# Module_blk.net
KiCad netlist of a schematic drawn in Altium Designer
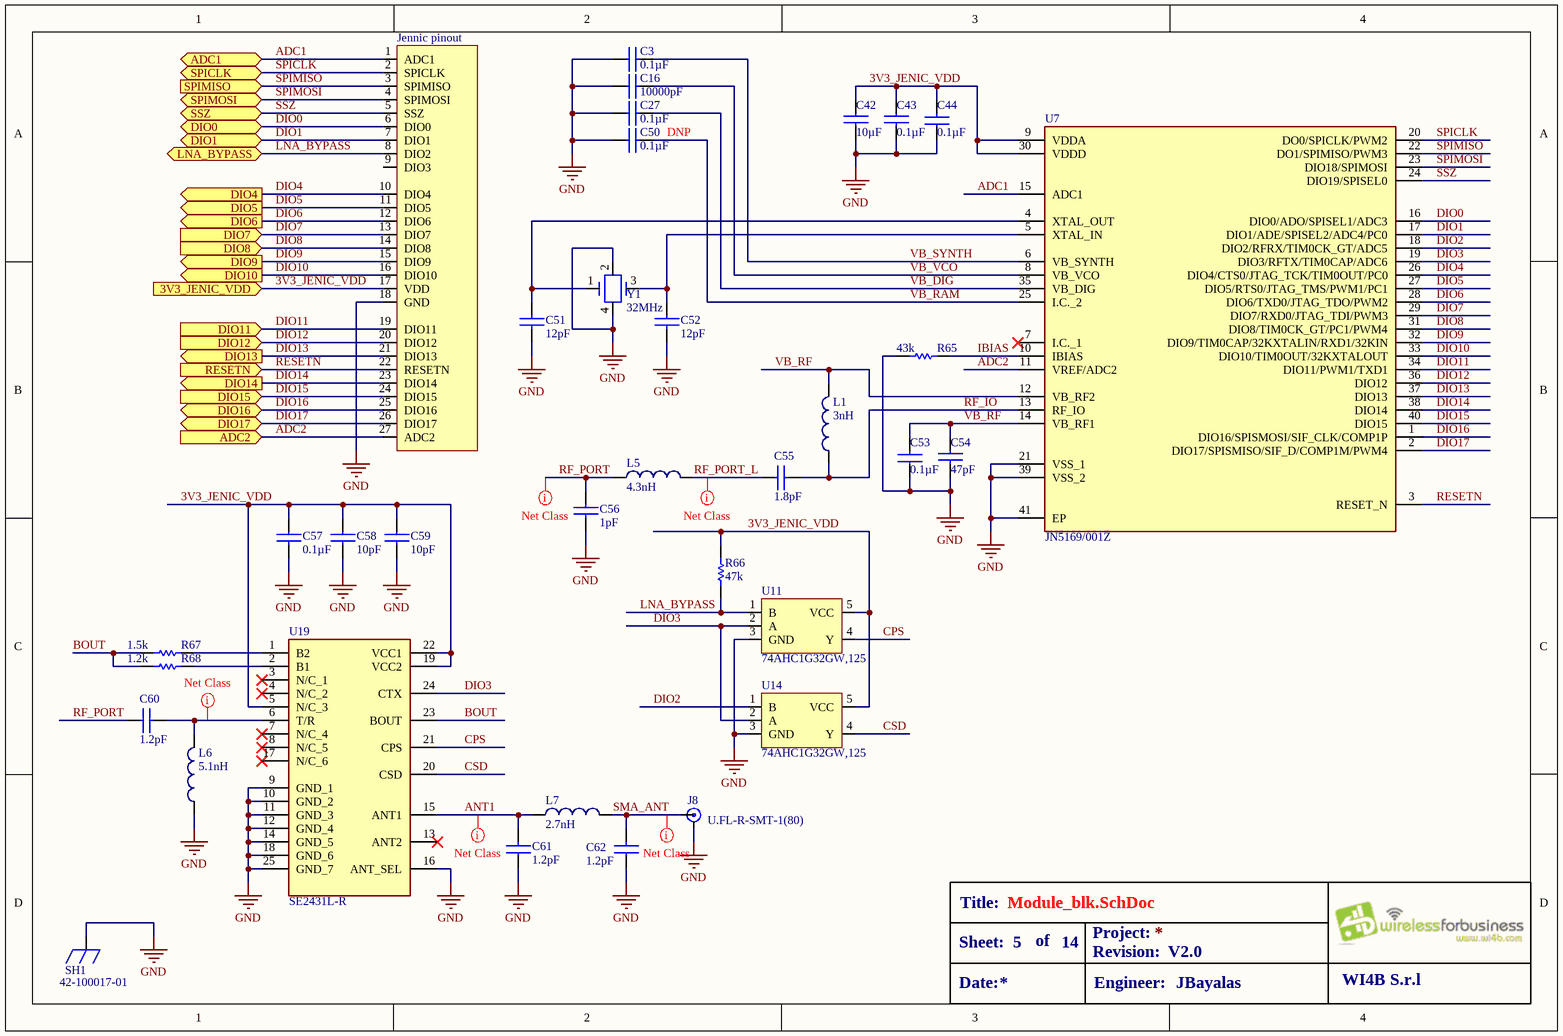
[diagram p0: Module_blk.SchDoc]

(export (version "E")
  (design (tool "Eeschema 10.0.6"))
  (components
    (comp (ref "C3")
      (value "0.1µF")
      (footprint "C0402")
      (description "CAP CER 0.1UF 50V X7R 0402")
      (fields (field (name "MPN") "GRM155R71H104ME14D"))
      (libsource (lib "Capacitor") (part "GRM155R71H104ME14D"))
    )
    (comp (ref "C16")
      (value "10000pF")
      (footprint "C0402")
      (description "CAP CER 10000PF 25V X7R 0402")
      (fields (field (name "MPN") "GRM155R71E103KA01D"))
      (libsource (lib "Capacitor") (part "GRM155R71E103KA01D"))
    )
    (comp (ref "C27")
      (value "0.1µF")
      (footprint "C0402")
      (description "CAP CER 0.1UF 50V X7R 0402")
      (fields (field (name "MPN") "GRM155R71H104ME14D"))
      (libsource (lib "Capacitor") (part "GRM155R71H104ME14D"))
    )
    (comp (ref "C42")
      (value "10µF")
      (footprint "CAPC2012X135N")
      (description "CAP CER 10UF 10V X5R 0805")
      (fields (field (name "MPN") "GRT21BR61A106KE01L"))
      (libsource (lib "Capacitor") (part "GRT21BR61A106KE01L"))
    )
    (comp (ref "C43")
      (value "0.1µF")
      (footprint "C0402")
      (description "CAP CER 0.1UF 50V X7R 0402")
      (fields (field (name "MPN") "GRM155R71H104ME14D"))
      (libsource (lib "Capacitor") (part "GRM155R71H104ME14D"))
    )
    (comp (ref "C44")
      (value "0.1µF")
      (footprint "C0402")
      (description "CAP CER 0.1UF 50V X7R 0402")
      (fields (field (name "MPN") "GRM155R71H104ME14D"))
      (libsource (lib "Capacitor") (part "GRM155R71H104ME14D"))
    )
    (comp (ref "C50")
      (value "0.1µF")
      (footprint "C0402")
      (description "CAP CER 0.1UF 50V X7R 0402")
      (fields (field (name "MPN") "GRM155R71H104ME14D") (field (name "LOAD") "DNP"))
      (libsource (lib "Capacitor") (part "GRM155R71H104ME14D"))
    )
    (comp (ref "C51")
      (value "12pF")
      (footprint "CAPC1005X55N")
      (description "CAP CER 12PF 50V C0G/NP0 0402")
      (fields (field (name "MPN") "GRM1555C1H120JA01D"))
      (libsource (lib "Capacitor") (part "GRM1555C1H120JA01D"))
    )
    (comp (ref "C52")
      (value "12pF")
      (footprint "CAPC1005X55N")
      (description "CAP CER 12PF 50V C0G/NP0 0402")
      (fields (field (name "MPN") "GRM1555C1H120JA01D"))
      (libsource (lib "Capacitor") (part "GRM1555C1H120JA01D"))
    )
    (comp (ref "C53")
      (value "0.1µF")
      (footprint "C0402")
      (description "CAP CER 0.1UF 50V X7R 0402")
      (fields (field (name "MPN") "GRM155R71H104ME14D"))
      (libsource (lib "Capacitor") (part "GRM155R71H104ME14D"))
    )
    (comp (ref "C54")
      (value "47pF")
      (footprint "CAPC1005X55N")
      (description "CAP CER 47PF 50V C0G/NP0 0402")
      (fields (field (name "MPN") "GRM1555C1H470JA01D"))
      (libsource (lib "Capacitor") (part "GRM1555C1H470JA01D"))
    )
    (comp (ref "C55")
      (value "1.8pF")
      (footprint "CAPC1005X55N")
      (description "CAP CER 1.8PF 50V C0G/NP0 0402")
      (fields (field (name "MPN") "GRM1555C1H1R8CA01D"))
      (libsource (lib "Capacitor") (part "GRM1555C1H1R8CA01D"))
    )
    (comp (ref "C56")
      (value "1pF")
      (footprint "CAPC1005X55N")
      (description "CAP CER 1PF 50V C0G/NP0 0402")
      (fields (field (name "MPN") "GRM1555C1H1R0CA01D"))
      (libsource (lib "Capacitor") (part "GRM1555C1H1R0CA01D"))
    )
    (comp (ref "C57")
      (value "0.1µF")
      (footprint "C0402")
      (description "CAP CER 0.1UF 50V X7R 0402")
      (fields (field (name "MPN") "GRM155R71H104ME14D"))
      (libsource (lib "Capacitor") (part "GRM155R71H104ME14D"))
    )
    (comp (ref "C58")
      (value "10pF")
      (footprint "C0402")
      (description "CAP CER 10PF 50V 5% NP0 0402")
      (fields (field (name "MPN") "GRM1555C1H100JA01D"))
      (libsource (lib "Capacitor") (part "GRM1555C1H100JA01D"))
    )
    (comp (ref "C59")
      (value "10pF")
      (footprint "C0402")
      (description "CAP CER 10PF 50V 5% NP0 0402")
      (fields (field (name "MPN") "GRM1555C1H100JA01D"))
      (libsource (lib "Capacitor") (part "GRM1555C1H100JA01D"))
    )
    (comp (ref "C60")
      (value "1.2pF")
      (footprint "CAPC1005X55N")
      (description "CAP CER 1.2PF 50V C0G/NP0 0402")
      (fields (field (name "MPN") "GRM1555C1H1R2CA01D"))
      (libsource (lib "Capacitor") (part "GRM1555C1H1R2CA01D"))
    )
    (comp (ref "C61")
      (value "1.2pF")
      (footprint "CAPC1005X55N")
      (description "CAP CER 1.2PF 50V C0G/NP0 0402")
      (fields (field (name "MPN") "GRM1555C1H1R2CA01D"))
      (libsource (lib "Capacitor") (part "GRM1555C1H1R2CA01D"))
    )
    (comp (ref "C62")
      (value "1.2pF")
      (footprint "CAPC1005X55N")
      (description "CAP CER 1.2PF 50V C0G/NP0 0402")
      (fields (field (name "MPN") "GRM1555C1H1R2CA01D"))
      (libsource (lib "Capacitor") (part "GRM1555C1H1R2CA01D"))
    )
    (comp (ref "J8")
      (value "U.FL-R-SMT-1(80)")
      (footprint "HIROSE_U.FL-R-SMT")
      (description "RF Connectors / Coaxial Connectors SMT MALE RECEPT AU")
      (libsource (lib "Connector") (part "U.FL-R-SMT-1(80)"))
    )
    (comp (ref "Jennic pinout")
      (value "Jennic pinout")
      (footprint "JN516X PINOUT")
      (fields (field (name "MPN") "Jennic Pinout"))
      (libsource (lib "Miscellaneous") (part "Jennic pinout"))
    )
    (comp (ref "L1")
      (value "3nH")
      (footprint "INDC1005X45N")
      (description "FIXED IND 3NH 190MA 400 MOHM SMD")
      (fields (field (name "MPN") "LQP15MN3N0B02D"))
      (libsource (lib "Inductor") (part "LQP15MN3N0B02D"))
    )
    (comp (ref "L5")
      (value "4.3nH")
      (footprint "INDC1005X45N")
      (description "FIXED IND 4.3NH 160MA 600 MOHM")
      (fields (field (name "MPN") "LQP15MN4N3B02D"))
      (libsource (lib "Inductor") (part "LQP15MN4N3B02D"))
    )
    (comp (ref "L6")
      (value "5.1nH")
      (footprint "INDC1005X45N")
      (description "Inductor RF Chip ThFIXED IND 5.1NH 140MA 700 MOHM")
      (fields (field (name "MPN") "LQP15MN5N1B02D"))
      (libsource (lib "Inductor") (part "LQP15MN5N1B02D"))
    )
    (comp (ref "L7")
      (value "2.7nH")
      (footprint "INDC1005X45N")
      (description "FIXED IND 2.7NH 220MA 300 MOHM")
      (fields (field (name "MPN") "LQP15MN2N7B02D"))
      (libsource (lib "Inductor") (part "LQP15MN2N7B02D"))
    )
    (comp (ref "R65")
      (value "43k")
      (footprint "RESC1005X40N")
      (description "RES SMD 43K OHM 1% 1/16W 0402")
      (fields (field (name "MPN") "RC0402FR-0743KL"))
      (libsource (lib "Res") (part "RC0402FR-0743KL"))
    )
    (comp (ref "R66")
      (value "47k")
      (footprint "R0402")
      (description "RES SMD 47K OHM 1% 1/16W 0402")
      (fields (field (name "MPN") "RC0402FR-0747KL"))
      (libsource (lib "Res") (part "RC0402FR-0747KL"))
    )
    (comp (ref "R67")
      (value "1.5k")
      (footprint "RESC1005X40N")
      (description "RES SMD 1.5K OHM 1% 1/16W 0402")
      (fields (field (name "MPN") "RC0402FR-071K5L"))
      (libsource (lib "Res") (part "RC0402FR-071K5L"))
    )
    (comp (ref "R68")
      (value "1.2k")
      (footprint "RESC1005X40N")
      (description "RES SMD 1.2K OHM 1% 1/16W 0402")
      (fields (field (name "MPN") "RC0402FR-071K2L"))
      (libsource (lib "Res") (part "RC0402FR-071K2L"))
    )
    (comp (ref "SH1")
      (value "42-100017-01")
      (footprint "42-100017-01(Shield)")
      (description "Shield")
      (libsource (lib "Miscellaneous") (part "42-100017-01"))
    )
    (comp (ref "U7")
      (value "JN5169/001Z")
      (footprint "QFN50P600X600X100-41N")
      (description "IC RF TXRX+MCU 802.15.4 40-VFQFN")
      (libsource (lib "IC") (part "JN5169/001Z"))
    )
    (comp (ref "U11")
      (value "74AHC1G32GW,125")
      (footprint "SOT65P210X110-5N")
      (description "IC GATE OR 1CH 2-INP 5TSSOP")
      (libsource (lib "IC") (part "74AHC1G32GW,125"))
    )
    (comp (ref "U14")
      (value "74AHC1G32GW,125")
      (footprint "SOT65P210X110-5N")
      (description "IC GATE OR 1CH 2-INP 5TSSOP")
      (libsource (lib "IC") (part "74AHC1G32GW,125"))
    )
    (comp (ref "U19")
      (value "SE2431L-R")
      (footprint "QFN40P300X400X90-25N-D")
      (description "IC RF FRONT END MOD 2.4GHZ 24QFN")
      (libsource (lib "IC") (part "SE2431L-R"))
    )
    (comp (ref "Y1")
      (value "32MHz")
      (footprint "OSCCC320X250X80L75X100N")
      (description "CRYSTAL 32.0000MHZ 9PF SMD")
      (fields (field (name "MPN") "ABM8-32.000MHZ-9-D1G-T"))
      (libsource (lib "Crystal") (part "ABM8-32.000MHZ-9-D1G-T"))
    )
  )
  (nets
    (net (code "1") (name "/3V3_JENIC_VDD") (class "Default")
      (node (ref "C42") (pin "1") (pinfunction "1_1") (pintype "passive"))
      (node (ref "C43") (pin "1") (pinfunction "1_1") (pintype "passive"))
      (node (ref "C44") (pin "2") (pinfunction "2_2") (pintype "passive"))
      (node (ref "C57") (pin "1") (pinfunction "1_1") (pintype "passive"))
      (node (ref "C58") (pin "1") (pinfunction "1_1") (pintype "passive"))
      (node (ref "C59") (pin "1") (pinfunction "1_1") (pintype "passive"))
      (node (ref "Jennic pinout") (pin "17") (pinfunction "VDD_17") (pintype "passive"))
      (node (ref "R66") (pin "2") (pinfunction "2_2") (pintype "passive"))
      (node (ref "U11") (pin "5") (pinfunction "VCC_5") (pintype "passive"))
      (node (ref "U14") (pin "5") (pinfunction "VCC_5") (pintype "passive"))
      (node (ref "U19") (pin "19") (pinfunction "VCC2_19") (pintype "passive"))
      (node (ref "U19") (pin "22") (pinfunction "VCC1_22") (pintype "passive"))
      (node (ref "U19") (pin "5") (pinfunction "N/C_3_5") (pintype "passive"))
      (node (ref "U7") (pin "30") (pinfunction "VDDD_30") (pintype "passive"))
      (node (ref "U7") (pin "9") (pinfunction "VDDA_9") (pintype "passive"))
    )
    (net (code "2") (name "/ADC1") (class "Default")
      (node (ref "Jennic pinout") (pin "1") (pinfunction "ADC1_1") (pintype "passive"))
      (node (ref "U7") (pin "15") (pinfunction "ADC1_15") (pintype "passive"))
    )
    (net (code "3") (name "/ADC2") (class "Default")
      (node (ref "Jennic pinout") (pin "27") (pinfunction "ADC2_27") (pintype "passive"))
      (node (ref "U7") (pin "11") (pinfunction "VREF/ADC2_11") (pintype "passive"))
    )
    (net (code "4") (name "/ANT1") (class "Default")
      (node (ref "C61") (pin "2") (pinfunction "2_2") (pintype "passive"))
      (node (ref "L7") (pin "2") (pinfunction "2_2") (pintype "passive"))
      (node (ref "U19") (pin "15") (pinfunction "ANT1_15") (pintype "passive"))
    )
    (net (code "5") (name "/BOUT") (class "Default")
      (node (ref "R67") (pin "1") (pinfunction "1_1") (pintype "passive"))
      (node (ref "R68") (pin "1") (pinfunction "1_1") (pintype "passive"))
      (node (ref "U19") (pin "23") (pinfunction "BOUT_23") (pintype "passive"))
    )
    (net (code "6") (name "/CPS") (class "Default")
      (node (ref "U11") (pin "4") (pinfunction "Y_4") (pintype "passive"))
      (node (ref "U19") (pin "21") (pinfunction "CPS_21") (pintype "passive"))
    )
    (net (code "7") (name "/CSD") (class "Default")
      (node (ref "U14") (pin "4") (pinfunction "Y_4") (pintype "passive"))
      (node (ref "U19") (pin "20") (pinfunction "CSD_20") (pintype "passive"))
    )
    (net (code "8") (name "/DIO0") (class "Default")
      (node (ref "Jennic pinout") (pin "6") (pinfunction "DIO0_6") (pintype "passive"))
      (node (ref "U7") (pin "16") (pinfunction "DIO0/ADO/SPISEL1/ADC3_16") (pintype "passive"))
    )
    (net (code "9") (name "/DIO1") (class "Default")
      (node (ref "Jennic pinout") (pin "7") (pinfunction "DIO1_7") (pintype "passive"))
      (node (ref "U7") (pin "17") (pinfunction "DIO1/ADE/SPISEL2/ADC4/PC0_17") (pintype "passive"))
    )
    (net (code "10") (name "/DIO2") (class "Default")
      (node (ref "U14") (pin "1") (pinfunction "B_1") (pintype "passive"))
      (node (ref "U7") (pin "18") (pinfunction "DIO2/RFRX/TIM0CK_GT/ADC5_18") (pintype "passive"))
    )
    (net (code "11") (name "/DIO3") (class "Default")
      (node (ref "U11") (pin "2") (pinfunction "A_2") (pintype "passive"))
      (node (ref "U14") (pin "2") (pinfunction "A_2") (pintype "passive"))
      (node (ref "U19") (pin "24") (pinfunction "CTX_24") (pintype "passive"))
      (node (ref "U7") (pin "19") (pinfunction "DIO3/RFTX/TIM0CAP/ADC6_19") (pintype "passive"))
    )
    (net (code "12") (name "/DIO4") (class "Default")
      (node (ref "Jennic pinout") (pin "10") (pinfunction "DIO4_10") (pintype "passive"))
      (node (ref "U7") (pin "26") (pinfunction "DIO4/CTS0/JTAG_TCK/TIM0OUT/PC0_26") (pintype "passive"))
    )
    (net (code "13") (name "/DIO5") (class "Default")
      (node (ref "Jennic pinout") (pin "11") (pinfunction "DIO5_11") (pintype "passive"))
      (node (ref "U7") (pin "27") (pinfunction "DIO5/RTS0/JTAG_TMS/PWM1/PC1_27") (pintype "passive"))
    )
    (net (code "14") (name "/DIO6") (class "Default")
      (node (ref "Jennic pinout") (pin "12") (pinfunction "DIO6_12") (pintype "passive"))
      (node (ref "U7") (pin "28") (pinfunction "DIO6/TXD0/JTAG_TDO/PWM2_28") (pintype "passive"))
    )
    (net (code "15") (name "/DIO7") (class "Default")
      (node (ref "Jennic pinout") (pin "13") (pinfunction "DIO7_13") (pintype "passive"))
      (node (ref "U7") (pin "29") (pinfunction "DIO7/RXD0/JTAG_TDI/PWM3_29") (pintype "passive"))
    )
    (net (code "16") (name "/DIO8") (class "Default")
      (node (ref "Jennic pinout") (pin "14") (pinfunction "DIO8_14") (pintype "passive"))
      (node (ref "U7") (pin "31") (pinfunction "DIO8/TIM0CK_GT/PC1/PWM4_31") (pintype "passive"))
    )
    (net (code "17") (name "/DIO9") (class "Default")
      (node (ref "Jennic pinout") (pin "15") (pinfunction "DIO9_15") (pintype "passive"))
      (node (ref "U7") (pin "32") (pinfunction "DIO9/TIM0CAP/32KXTALIN/RXD1/32KIN_32") (pintype "passive"))
    )
    (net (code "18") (name "/DIO10") (class "Default")
      (node (ref "Jennic pinout") (pin "16") (pinfunction "DIO10_16") (pintype "passive"))
      (node (ref "U7") (pin "33") (pinfunction "DIO10/TIM0OUT/32KXTALOUT_33") (pintype "passive"))
    )
    (net (code "19") (name "/DIO11") (class "Default")
      (node (ref "Jennic pinout") (pin "19") (pinfunction "DIO11_19") (pintype "passive"))
      (node (ref "U7") (pin "34") (pinfunction "DIO11/PWM1/TXD1_34") (pintype "passive"))
    )
    (net (code "20") (name "/DIO12") (class "Default")
      (node (ref "Jennic pinout") (pin "20") (pinfunction "DIO12_20") (pintype "passive"))
      (node (ref "U7") (pin "36") (pinfunction "DIO12_36") (pintype "passive"))
    )
    (net (code "21") (name "/DIO13") (class "Default")
      (node (ref "Jennic pinout") (pin "21") (pinfunction "DIO13_21") (pintype "passive"))
      (node (ref "U7") (pin "37") (pinfunction "DIO13_37") (pintype "passive"))
    )
    (net (code "22") (name "/DIO14") (class "Default")
      (node (ref "Jennic pinout") (pin "23") (pinfunction "DIO14_23") (pintype "passive"))
      (node (ref "U7") (pin "38") (pinfunction "DIO14_38") (pintype "passive"))
    )
    (net (code "23") (name "/DIO15") (class "Default")
      (node (ref "Jennic pinout") (pin "24") (pinfunction "DIO15_24") (pintype "passive"))
      (node (ref "U7") (pin "40") (pinfunction "DIO15_40") (pintype "passive"))
    )
    (net (code "24") (name "/DIO16") (class "Default")
      (node (ref "Jennic pinout") (pin "25") (pinfunction "DIO16_25") (pintype "passive"))
      (node (ref "U7") (pin "1") (pinfunction "DIO16/SPISMOSI/SIF_CLK/COMP1P_1") (pintype "passive"))
    )
    (net (code "25") (name "/DIO17") (class "Default")
      (node (ref "Jennic pinout") (pin "26") (pinfunction "DIO17_26") (pintype "passive"))
      (node (ref "U7") (pin "2") (pinfunction "DIO17/SPISMISO/SIF_D/COMP1M/PWM4_2") (pintype "passive"))
    )
    (net (code "26") (name "/IBIAS") (class "Default")
      (node (ref "R65") (pin "2") (pinfunction "2_2") (pintype "passive"))
      (node (ref "U7") (pin "10") (pinfunction "IBIAS_10") (pintype "passive"))
    )
    (net (code "27") (name "/LNA_BYPASS") (class "Default")
      (node (ref "Jennic pinout") (pin "8") (pinfunction "DIO2_8") (pintype "passive"))
      (node (ref "R66") (pin "1") (pinfunction "1_1") (pintype "passive"))
      (node (ref "U11") (pin "1") (pinfunction "B_1") (pintype "passive"))
    )
    (net (code "28") (name "/RESETN") (class "Default")
      (node (ref "Jennic pinout") (pin "22") (pinfunction "RESETN_22") (pintype "passive"))
      (node (ref "U7") (pin "3") (pinfunction "RESET_N_3") (pintype "passive"))
    )
    (net (code "29") (name "/RF_IO") (class "Default")
      (node (ref "C55") (pin "2") (pinfunction "2_2") (pintype "passive"))
      (node (ref "L1") (pin "2") (pinfunction "2_2") (pintype "passive"))
      (node (ref "U7") (pin "13") (pinfunction "RF_IO_13") (pintype "passive"))
    )
    (net (code "30") (name "/RF_PORT") (class "Default")
      (node (ref "C56") (pin "1") (pinfunction "1_1") (pintype "passive"))
      (node (ref "C60") (pin "1") (pinfunction "1_1") (pintype "passive"))
      (node (ref "L5") (pin "2") (pinfunction "2_2") (pintype "passive"))
    )
    (net (code "31") (name "/RF_PORT_L") (class "Default")
      (node (ref "C55") (pin "1") (pinfunction "1_1") (pintype "passive"))
      (node (ref "L5") (pin "1") (pinfunction "1_1") (pintype "passive"))
    )
    (net (code "32") (name "/SMA_ANT") (class "Default")
      (node (ref "C62") (pin "2") (pinfunction "2_2") (pintype "passive"))
      (node (ref "J8") (pin "1") (pinfunction "SIGNAL_1") (pintype "passive"))
      (node (ref "L7") (pin "1") (pinfunction "1_1") (pintype "passive"))
    )
    (net (code "33") (name "/SPICLK") (class "Default")
      (node (ref "Jennic pinout") (pin "2") (pinfunction "SPICLK_2") (pintype "passive"))
      (node (ref "U7") (pin "20") (pinfunction "DO0/SPICLK/PWM2_20") (pintype "passive"))
    )
    (net (code "34") (name "/SPIMISO") (class "Default")
      (node (ref "Jennic pinout") (pin "3") (pinfunction "SPIMISO_3") (pintype "passive"))
      (node (ref "U7") (pin "22") (pinfunction "DO1/SPIMISO/PWM3_22") (pintype "passive"))
    )
    (net (code "35") (name "/SPIMOSI") (class "Default")
      (node (ref "Jennic pinout") (pin "4") (pinfunction "SPIMOSI_4") (pintype "passive"))
      (node (ref "U7") (pin "23") (pinfunction "DIO18/SPIMOSI_23") (pintype "passive"))
    )
    (net (code "36") (name "/SSZ") (class "Default")
      (node (ref "Jennic pinout") (pin "5") (pinfunction "SSZ_5") (pintype "passive"))
      (node (ref "U7") (pin "24") (pinfunction "DIO19/SPISEL0_24") (pintype "passive"))
    )
    (net (code "37") (name "/VB_DIG") (class "Default")
      (node (ref "C27") (pin "2") (pinfunction "2_2") (pintype "passive"))
      (node (ref "U7") (pin "35") (pinfunction "VB_DIG_35") (pintype "passive"))
    )
    (net (code "38") (name "/VB_RAM") (class "Default")
      (node (ref "C50") (pin "2") (pinfunction "2_2") (pintype "passive"))
      (node (ref "U7") (pin "25") (pinfunction "I.C._2_25") (pintype "passive"))
    )
    (net (code "39") (name "/VB_RF") (class "Default")
      (node (ref "C53") (pin "2") (pinfunction "2_2") (pintype "passive"))
      (node (ref "C54") (pin "1") (pinfunction "1_1") (pintype "passive"))
      (node (ref "L1") (pin "1") (pinfunction "1_1") (pintype "passive"))
      (node (ref "U7") (pin "12") (pinfunction "VB_RF2_12") (pintype "passive"))
      (node (ref "U7") (pin "14") (pinfunction "VB_RF1_14") (pintype "passive"))
    )
    (net (code "40") (name "/VB_SYNTH") (class "Default")
      (node (ref "C3") (pin "2") (pinfunction "2_2") (pintype "passive"))
      (node (ref "U7") (pin "6") (pinfunction "VB_SYNTH_6") (pintype "passive"))
    )
    (net (code "41") (name "/VB_VCO") (class "Default")
      (node (ref "C16") (pin "2") (pinfunction "2_2") (pintype "passive"))
      (node (ref "U7") (pin "8") (pinfunction "VB_VCO_8") (pintype "passive"))
    )
    (net (code "42") (name "GND") (class "Default")
      (node (ref "C16") (pin "1") (pinfunction "1_1") (pintype "passive"))
      (node (ref "C27") (pin "1") (pinfunction "1_1") (pintype "passive"))
      (node (ref "C3") (pin "1") (pinfunction "1_1") (pintype "passive"))
      (node (ref "C42") (pin "2") (pinfunction "2_2") (pintype "passive"))
      (node (ref "C43") (pin "2") (pinfunction "2_2") (pintype "passive"))
      (node (ref "C44") (pin "1") (pinfunction "1_1") (pintype "passive"))
      (node (ref "C50") (pin "1") (pinfunction "1_1") (pintype "passive"))
      (node (ref "C51") (pin "2") (pinfunction "2_2") (pintype "passive"))
      (node (ref "C52") (pin "2") (pinfunction "2_2") (pintype "passive"))
      (node (ref "C53") (pin "1") (pinfunction "1_1") (pintype "passive"))
      (node (ref "C54") (pin "2") (pinfunction "2_2") (pintype "passive"))
      (node (ref "C56") (pin "2") (pinfunction "2_2") (pintype "passive"))
      (node (ref "C57") (pin "2") (pinfunction "2_2") (pintype "passive"))
      (node (ref "C58") (pin "2") (pinfunction "2_2") (pintype "passive"))
      (node (ref "C59") (pin "2") (pinfunction "2_2") (pintype "passive"))
      (node (ref "C61") (pin "1") (pinfunction "1_1") (pintype "passive"))
      (node (ref "C62") (pin "1") (pinfunction "1_1") (pintype "passive"))
      (node (ref "J8") (pin "2") (pinfunction "GND_2") (pintype "passive"))
      (node (ref "Jennic pinout") (pin "18") (pinfunction "GND_18") (pintype "passive"))
      (node (ref "L6") (pin "2") (pinfunction "2_2") (pintype "passive"))
      (node (ref "R65") (pin "1") (pinfunction "1_1") (pintype "passive"))
      (node (ref "SH1") (pin "1") (pinfunction "1_1") (pintype "passive"))
      (node (ref "U11") (pin "3") (pinfunction "GND_3") (pintype "passive"))
      (node (ref "U14") (pin "3") (pinfunction "GND_3") (pintype "passive"))
      (node (ref "U19") (pin "10") (pinfunction "GND_2_10") (pintype "passive"))
      (node (ref "U19") (pin "11") (pinfunction "GND_3_11") (pintype "passive"))
      (node (ref "U19") (pin "12") (pinfunction "GND_4_12") (pintype "passive"))
      (node (ref "U19") (pin "14") (pinfunction "GND_5_14") (pintype "passive"))
      (node (ref "U19") (pin "16") (pinfunction "ANT_SEL_16") (pintype "passive"))
      (node (ref "U19") (pin "18") (pinfunction "GND_6_18") (pintype "passive"))
      (node (ref "U19") (pin "25") (pinfunction "GND_7_25") (pintype "passive"))
      (node (ref "U19") (pin "9") (pinfunction "GND_1_9") (pintype "passive"))
      (node (ref "U7") (pin "21") (pinfunction "VSS_1_21") (pintype "passive"))
      (node (ref "U7") (pin "39") (pinfunction "VSS_2_39") (pintype "passive"))
      (node (ref "U7") (pin "41") (pinfunction "EP_41") (pintype "passive"))
      (node (ref "Y1") (pin "2") (pinfunction "2_2") (pintype "passive"))
      (node (ref "Y1") (pin "4") (pinfunction "4_4") (pintype "passive"))
    )
    (net (code "43") (name "Net-(U7-XTAL_IN)") (class "Default")
      (node (ref "C52") (pin "1") (pinfunction "1_1") (pintype "passive"))
      (node (ref "U7") (pin "5") (pinfunction "XTAL_IN_5") (pintype "passive"))
      (node (ref "Y1") (pin "3") (pinfunction "3_3") (pintype "passive"))
    )
    (net (code "44") (name "Net-(U7-XTAL_OUT)") (class "Default")
      (node (ref "C51") (pin "1") (pinfunction "1_1") (pintype "passive"))
      (node (ref "U7") (pin "4") (pinfunction "XTAL_OUT_4") (pintype "passive"))
      (node (ref "Y1") (pin "1") (pinfunction "1_1") (pintype "passive"))
    )
    (net (code "45") (name "Net-(U19-B1)") (class "Default")
      (node (ref "R68") (pin "2") (pinfunction "2_2") (pintype "passive"))
      (node (ref "U19") (pin "2") (pinfunction "B1_2") (pintype "passive"))
    )
    (net (code "46") (name "Net-(U19-B2)") (class "Default")
      (node (ref "R67") (pin "2") (pinfunction "2_2") (pintype "passive"))
      (node (ref "U19") (pin "1") (pinfunction "B2_1") (pintype "passive"))
    )
    (net (code "47") (name "Net-(U19-T{slash}R)") (class "Default")
      (node (ref "C60") (pin "2") (pinfunction "2_2") (pintype "passive"))
      (node (ref "L6") (pin "1") (pinfunction "1_1") (pintype "passive"))
      (node (ref "U19") (pin "6") (pinfunction "T/R_6") (pintype "passive"))
    )
    (net (code "48") (name "unconnected-(Jennic pinout-DIO3-Pad9)") (class "Default")
      (node (ref "Jennic pinout") (pin "9") (pinfunction "DIO3_9") (pintype "passive"))
    )
    (net (code "49") (name "unconnected-(U7-I.C._1-Pad7)") (class "Default")
      (node (ref "U7") (pin "7") (pinfunction "I.C._1_7") (pintype "passive+no_connect"))
    )
    (net (code "50") (name "unconnected-(U19-ANT2-Pad13)") (class "Default")
      (node (ref "U19") (pin "13") (pinfunction "ANT2_13") (pintype "passive+no_connect"))
    )
    (net (code "51") (name "unconnected-(U19-N{slash}C_1-Pad3)") (class "Default")
      (node (ref "U19") (pin "3") (pinfunction "N/C_1_3") (pintype "passive+no_connect"))
    )
    (net (code "52") (name "unconnected-(U19-N{slash}C_2-Pad4)") (class "Default")
      (node (ref "U19") (pin "4") (pinfunction "N/C_2_4") (pintype "passive+no_connect"))
    )
    (net (code "53") (name "unconnected-(U19-N{slash}C_4-Pad7)") (class "Default")
      (node (ref "U19") (pin "7") (pinfunction "N/C_4_7") (pintype "passive+no_connect"))
    )
    (net (code "54") (name "unconnected-(U19-N{slash}C_5-Pad8)") (class "Default")
      (node (ref "U19") (pin "8") (pinfunction "N/C_5_8") (pintype "passive+no_connect"))
    )
    (net (code "55") (name "unconnected-(U19-N{slash}C_6-Pad17)") (class "Default")
      (node (ref "U19") (pin "17") (pinfunction "N/C_6_17") (pintype "passive+no_connect"))
    )
  )
)
